# EspProgrammer.net
KiCad netlist of a schematic drawn in EAGLE
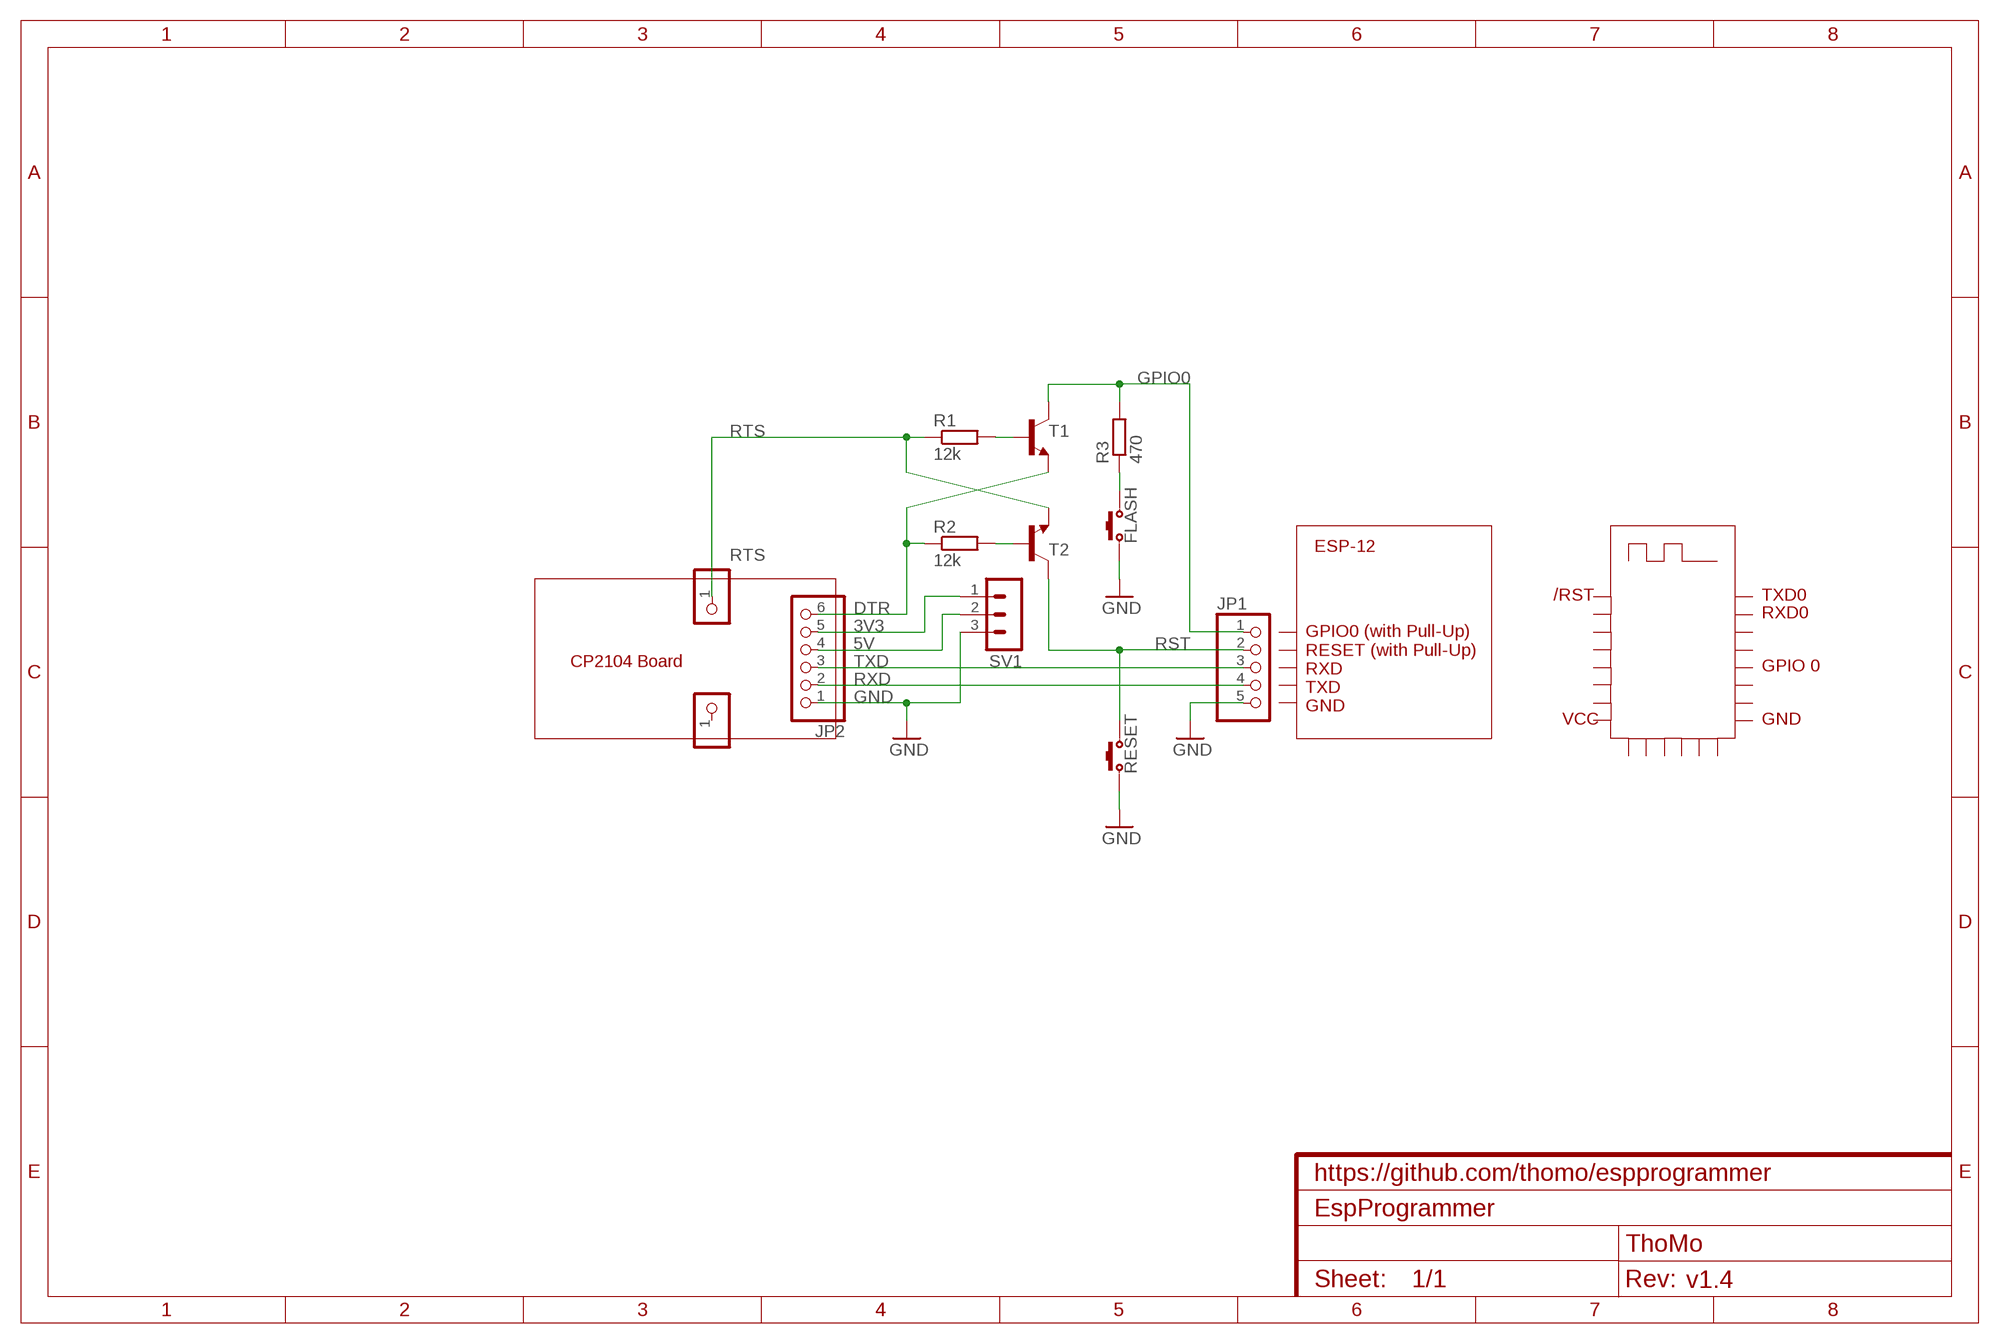
[diagram p0: schematic, sheet 1]

(export (version "E")
  (design (tool "Eeschema 10.0.6"))
  (components
    (comp (ref "FLASH")
      (value "KEY")
      (footprint "eagle-import:SMD-BUTTON")
      (libsource (lib "eagle-import") (part "KEY"))
    )
    (comp (ref "JP1")
      (value "PINHD-1X5/90")
      (footprint "eagle-import:1X05_90")
      (libsource (lib "eagle-import") (part "PINHD-1X5/90"))
    )
    (comp (ref "JP2")
      (value "PINHD-1X6")
      (footprint "eagle-import:1X06")
      (libsource (lib "eagle-import") (part "PINHD-1X6"))
    )
    (comp (ref "LSP2")
      (value "PINHD-1X1")
      (footprint "eagle-import:1X01")
      (libsource (lib "eagle-import") (part "PINHD-1X1"))
    )
    (comp (ref "LSP3")
      (value "PINHD-1X1")
      (footprint "eagle-import:1X01")
      (libsource (lib "eagle-import") (part "PINHD-1X1"))
    )
    (comp (ref "R1")
      (value "12k")
      (footprint "eagle-import:R1206")
      (libsource (lib "eagle-import") (part "R-EU_R1206"))
    )
    (comp (ref "R2")
      (value "12k")
      (footprint "eagle-import:R1206")
      (libsource (lib "eagle-import") (part "R-EU_R1206"))
    )
    (comp (ref "R3")
      (value "470")
      (footprint "eagle-import:R1206")
      (libsource (lib "eagle-import") (part "R-EU_R1206"))
    )
    (comp (ref "RESET")
      (value "KEY")
      (footprint "eagle-import:SMD-BUTTON")
      (libsource (lib "eagle-import") (part "KEY"))
    )
    (comp (ref "SV1")
      (value "MA03-1")
      (footprint "eagle-import:MA03-1")
      (libsource (lib "eagle-import") (part "MA03-1"))
    )
    (comp (ref "T1")
      (value "BC817-40LT1SMD")
      (footprint "eagle-import:SOT23-BEC")
      (libsource (lib "eagle-import") (part "BC817SMD-40LT1"))
    )
    (comp (ref "T2")
      (value "BC817-40LT1SMD")
      (footprint "eagle-import:SOT23-BEC")
      (libsource (lib "eagle-import") (part "BC817SMD-40LT1"))
    )
  )
  (nets
    (net (code "1") (name "/3V3") (class "Default")
      (node (ref "JP2") (pin "5") (pinfunction "5_5") (pintype "passive"))
      (node (ref "SV1") (pin "1") (pinfunction "1_1") (pintype "passive"))
    )
    (net (code "2") (name "/5V") (class "Default")
      (node (ref "JP2") (pin "4") (pinfunction "4_4") (pintype "passive"))
      (node (ref "SV1") (pin "2") (pinfunction "2_2") (pintype "passive"))
    )
    (net (code "3") (name "/DTR") (class "Default")
      (node (ref "JP2") (pin "6") (pinfunction "6_6") (pintype "passive"))
      (node (ref "R2") (pin "1") (pinfunction "1_1") (pintype "passive"))
      (node (ref "T1") (pin "E") (pinfunction "E_E") (pintype "passive"))
    )
    (net (code "4") (name "/GPIO0") (class "Default")
      (node (ref "JP1") (pin "1") (pinfunction "1_1") (pintype "passive"))
      (node (ref "R3") (pin "2") (pinfunction "2_2") (pintype "passive"))
      (node (ref "T1") (pin "C") (pinfunction "C_C") (pintype "passive"))
    )
    (net (code "5") (name "/RST") (class "Default")
      (node (ref "JP1") (pin "2") (pinfunction "2_2") (pintype "passive"))
      (node (ref "RESET") (pin "1") (pinfunction "1_1") (pintype "passive"))
      (node (ref "T2") (pin "C") (pinfunction "C_C") (pintype "passive"))
    )
    (net (code "6") (name "/RTS") (class "Default")
      (node (ref "LSP3") (pin "1") (pinfunction "1_1") (pintype "passive"))
      (node (ref "R1") (pin "1") (pinfunction "1_1") (pintype "passive"))
      (node (ref "T2") (pin "E") (pinfunction "E_E") (pintype "passive"))
    )
    (net (code "7") (name "/RXD") (class "Default")
      (node (ref "JP1") (pin "4") (pinfunction "4_4") (pintype "passive"))
      (node (ref "JP2") (pin "2") (pinfunction "2_2") (pintype "passive"))
    )
    (net (code "8") (name "/TXD") (class "Default")
      (node (ref "JP1") (pin "3") (pinfunction "3_3") (pintype "passive"))
      (node (ref "JP2") (pin "3") (pinfunction "3_3") (pintype "passive"))
    )
    (net (code "9") (name "GND") (class "Default")
      (node (ref "FLASH") (pin "2") (pinfunction "2_2") (pintype "passive"))
      (node (ref "JP1") (pin "5") (pinfunction "5_5") (pintype "passive"))
      (node (ref "JP2") (pin "1") (pinfunction "1_1") (pintype "passive"))
      (node (ref "RESET") (pin "2") (pinfunction "2_2") (pintype "passive"))
      (node (ref "SV1") (pin "3") (pinfunction "3_3") (pintype "passive"))
    )
    (net (code "10") (name "Net-(FLASH-Pad1)") (class "Default")
      (node (ref "FLASH") (pin "1") (pinfunction "1_1") (pintype "passive"))
      (node (ref "R3") (pin "1") (pinfunction "1_1") (pintype "passive"))
    )
    (net (code "11") (name "Net-(R1-Pad2)") (class "Default")
      (node (ref "R1") (pin "2") (pinfunction "2_2") (pintype "passive"))
      (node (ref "T1") (pin "B") (pinfunction "B_B") (pintype "passive"))
    )
    (net (code "12") (name "Net-(R2-Pad2)") (class "Default")
      (node (ref "R2") (pin "2") (pinfunction "2_2") (pintype "passive"))
      (node (ref "T2") (pin "B") (pinfunction "B_B") (pintype "passive"))
    )
    (net (code "13") (name "unconnected-(LSP2-Pad1)") (class "Default")
      (node (ref "LSP2") (pin "1") (pinfunction "1_1") (pintype "passive"))
    )
  )
)
